# swbar002.net
KiCad netlist of a schematic drawn in EAGLE
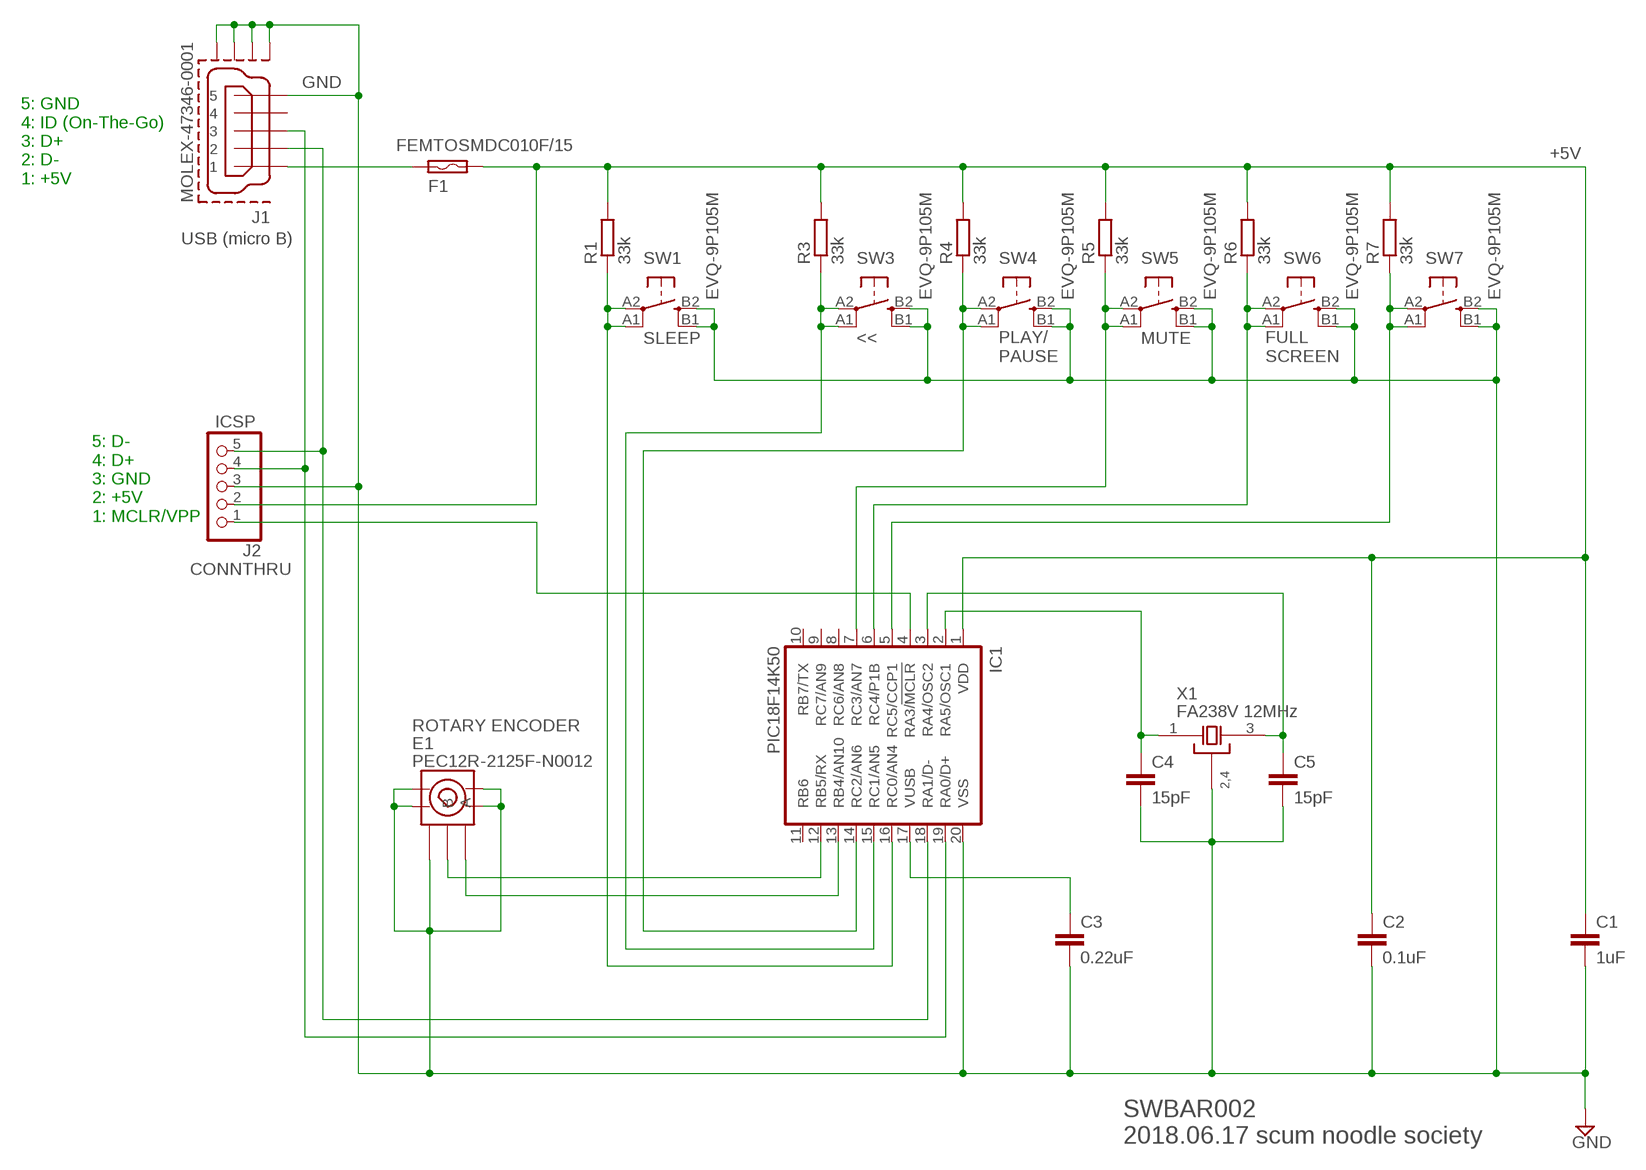
[diagram p0: schematic, sheet 1]

(export (version "E")
  (design (tool "Eeschema 10.0.6"))
  (components
    (comp (ref "C1")
      (value "1uF")
      (footprint "eagle-import:C0603K")
      (libsource (lib "eagle-import") (part "C-EUC0603K"))
    )
    (comp (ref "C2")
      (value "0.1uF")
      (footprint "eagle-import:C0603K")
      (libsource (lib "eagle-import") (part "C-EUC0603K"))
    )
    (comp (ref "C3")
      (value "0.22uF")
      (footprint "eagle-import:C0603K")
      (libsource (lib "eagle-import") (part "C-EUC0603K"))
    )
    (comp (ref "C4")
      (value "15pF")
      (footprint "eagle-import:C0603K")
      (libsource (lib "eagle-import") (part "C-EUC0603K"))
    )
    (comp (ref "C5")
      (value "15pF")
      (footprint "eagle-import:C0603K")
      (libsource (lib "eagle-import") (part "C-EUC0603K"))
    )
    (comp (ref "E1")
      (value "PEC12R-2125F-N0012")
      (footprint "eagle-import:PEC12R")
      (libsource (lib "eagle-import") (part "PEC12R-2125F-N0012"))
    )
    (comp (ref "F1")
      (value "FEMTOSMDC010F/15")
      (footprint "eagle-import:C0603K")
      (libsource (lib "eagle-import") (part "FEMTOSMDC010F/15"))
    )
    (comp (ref "IC1")
      (value "PIC18F14K50")
      (footprint "eagle-import:SSOP20")
      (libsource (lib "eagle-import") (part "PIC18F14K50"))
    )
    (comp (ref "J1")
      (value "MOLEX-47346-0001")
      (footprint "eagle-import:MOLEX-47364-0001")
      (libsource (lib "eagle-import") (part "MOLEX-47346-0001"))
    )
    (comp (ref "J2")
      (value "CONNTHRU")
      (footprint "eagle-import:1X05_CONNTHRU")
      (libsource (lib "eagle-import") (part "PINHD-1X51X05_CONNTHRU"))
    )
    (comp (ref "R1")
      (value "33k")
      (footprint "eagle-import:R0603")
      (libsource (lib "eagle-import") (part "R-EU_R0603"))
    )
    (comp (ref "R3")
      (value "33k")
      (footprint "eagle-import:R0603")
      (libsource (lib "eagle-import") (part "R-EU_R0603"))
    )
    (comp (ref "R4")
      (value "33k")
      (footprint "eagle-import:R0603")
      (libsource (lib "eagle-import") (part "R-EU_R0603"))
    )
    (comp (ref "R5")
      (value "33k")
      (footprint "eagle-import:R0603")
      (libsource (lib "eagle-import") (part "R-EU_R0603"))
    )
    (comp (ref "R6")
      (value "33k")
      (footprint "eagle-import:R0603")
      (libsource (lib "eagle-import") (part "R-EU_R0603"))
    )
    (comp (ref "R7")
      (value "33k")
      (footprint "eagle-import:R0603")
      (libsource (lib "eagle-import") (part "R-EU_R0603"))
    )
    (comp (ref "SW1")
      (value "EVQ-9P105M")
      (footprint "eagle-import:EVQ9P")
      (libsource (lib "eagle-import") (part "EVQ-9P105M"))
    )
    (comp (ref "SW3")
      (value "EVQ-9P105M")
      (footprint "eagle-import:EVQ9P")
      (libsource (lib "eagle-import") (part "EVQ-9P105M"))
    )
    (comp (ref "SW4")
      (value "EVQ-9P105M")
      (footprint "eagle-import:EVQ9P")
      (libsource (lib "eagle-import") (part "EVQ-9P105M"))
    )
    (comp (ref "SW5")
      (value "EVQ-9P105M")
      (footprint "eagle-import:EVQ9P")
      (libsource (lib "eagle-import") (part "EVQ-9P105M"))
    )
    (comp (ref "SW6")
      (value "EVQ-9P105M")
      (footprint "eagle-import:EVQ9P")
      (libsource (lib "eagle-import") (part "EVQ-9P105M"))
    )
    (comp (ref "SW7")
      (value "EVQ-9P105M")
      (footprint "eagle-import:EVQ9P")
      (libsource (lib "eagle-import") (part "EVQ-9P105M"))
    )
    (comp (ref "X1")
      (value "FA238V 12MHz")
      (footprint "eagle-import:XTAL_SMD_32X25")
      (libsource (lib "eagle-import") (part "FA-238V"))
    )
  )
  (nets
    (net (code "1") (name "/+5V") (class "Default")
      (node (ref "C1") (pin "1") (pinfunction "1_1") (pintype "passive"))
      (node (ref "C2") (pin "1") (pinfunction "1_1") (pintype "passive"))
      (node (ref "F1") (pin "2") (pinfunction "2_2") (pintype "passive"))
      (node (ref "IC1") (pin "1") (pinfunction "VDD_1") (pintype "power_in"))
      (node (ref "J2") (pin "2") (pinfunction "2_2") (pintype "passive"))
      (node (ref "R1") (pin "2") (pinfunction "2_2") (pintype "passive"))
      (node (ref "R3") (pin "2") (pinfunction "2_2") (pintype "passive"))
      (node (ref "R4") (pin "2") (pinfunction "2_2") (pintype "passive"))
      (node (ref "R5") (pin "2") (pinfunction "2_2") (pintype "passive"))
      (node (ref "R6") (pin "2") (pinfunction "2_2") (pintype "passive"))
      (node (ref "R7") (pin "2") (pinfunction "2_2") (pintype "passive"))
    )
    (net (code "2") (name "GND") (class "Default")
      (node (ref "C1") (pin "2") (pinfunction "2_2") (pintype "passive"))
      (node (ref "C2") (pin "2") (pinfunction "2_2") (pintype "passive"))
      (node (ref "C3") (pin "2") (pinfunction "2_2") (pintype "passive"))
      (node (ref "C4") (pin "2") (pinfunction "2_2") (pintype "passive"))
      (node (ref "C5") (pin "2") (pinfunction "2_2") (pintype "passive"))
      (node (ref "E1") (pin "GND@1") (pinfunction "GND_GND@1") (pintype "power_in"))
      (node (ref "E1") (pin "GND@2") (pinfunction "GND_GND@2") (pintype "power_in"))
      (node (ref "E1") (pin "GND@3") (pinfunction "GND_GND@3") (pintype "power_in"))
      (node (ref "E1") (pin "GND@4") (pinfunction "GND_GND@4") (pintype "power_in"))
      (node (ref "E1") (pin "GND@5") (pinfunction "GND_GND@5") (pintype "power_in"))
      (node (ref "IC1") (pin "20") (pinfunction "VSS_20") (pintype "power_in"))
      (node (ref "J1") (pin "5") (pinfunction "5_5") (pintype "input"))
      (node (ref "J1") (pin "GND1") (pinfunction "GND_GND1") (pintype "bidirectional"))
      (node (ref "J1") (pin "GND2") (pinfunction "GND_GND2") (pintype "bidirectional"))
      (node (ref "J1") (pin "GND3") (pinfunction "GND_GND3") (pintype "bidirectional"))
      (node (ref "J1") (pin "GND4") (pinfunction "GND_GND4") (pintype "bidirectional"))
      (node (ref "J2") (pin "3") (pinfunction "3_3") (pintype "passive"))
      (node (ref "SW1") (pin "B1") (pinfunction "G$S1_B1") (pintype "passive"))
      (node (ref "SW1") (pin "B2") (pinfunction "G$S2_B2") (pintype "passive"))
      (node (ref "SW3") (pin "B1") (pinfunction "G$S1_B1") (pintype "passive"))
      (node (ref "SW3") (pin "B2") (pinfunction "G$S2_B2") (pintype "passive"))
      (node (ref "SW4") (pin "B1") (pinfunction "G$S1_B1") (pintype "passive"))
      (node (ref "SW4") (pin "B2") (pinfunction "G$S2_B2") (pintype "passive"))
      (node (ref "SW5") (pin "B1") (pinfunction "G$S1_B1") (pintype "passive"))
      (node (ref "SW5") (pin "B2") (pinfunction "G$S2_B2") (pintype "passive"))
      (node (ref "SW6") (pin "B1") (pinfunction "G$S1_B1") (pintype "passive"))
      (node (ref "SW6") (pin "B2") (pinfunction "G$S2_B2") (pintype "passive"))
      (node (ref "SW7") (pin "B1") (pinfunction "G$S1_B1") (pintype "passive"))
      (node (ref "SW7") (pin "B2") (pinfunction "G$S2_B2") (pintype "passive"))
      (node (ref "X1") (pin "2") (pinfunction "GND_2") (pintype "power_in"))
      (node (ref "X1") (pin "4") (pinfunction "GND_4") (pintype "power_in"))
    )
    (net (code "3") (name "Net-(F1-Pad1)") (class "Default")
      (node (ref "F1") (pin "1") (pinfunction "1_1") (pintype "passive"))
      (node (ref "J1") (pin "1") (pinfunction "1_1") (pintype "input"))
    )
    (net (code "4") (name "Net-(IC1-RA0{slash}D+)") (class "Default")
      (node (ref "IC1") (pin "19") (pinfunction "RA0/D+_19") (pintype "bidirectional"))
      (node (ref "J1") (pin "3") (pinfunction "3_3") (pintype "input"))
      (node (ref "J2") (pin "4") (pinfunction "4_4") (pintype "passive"))
    )
    (net (code "5") (name "Net-(IC1-RA1{slash}D-)") (class "Default")
      (node (ref "IC1") (pin "18") (pinfunction "RA1/D-_18") (pintype "bidirectional"))
      (node (ref "J1") (pin "2") (pinfunction "2_2") (pintype "input"))
      (node (ref "J2") (pin "5") (pinfunction "5_5") (pintype "passive"))
    )
    (net (code "6") (name "Net-(IC1-RA3{slash}~{MCLR})") (class "Default")
      (node (ref "IC1") (pin "4") (pinfunction "RA3/~{MCLR}_4") (pintype "bidirectional"))
      (node (ref "J2") (pin "1") (pinfunction "1_1") (pintype "passive"))
    )
    (net (code "7") (name "Net-(IC1-RA4{slash}OSC2)") (class "Default")
      (node (ref "C5") (pin "1") (pinfunction "1_1") (pintype "passive"))
      (node (ref "IC1") (pin "3") (pinfunction "RA4/OSC2_3") (pintype "bidirectional"))
      (node (ref "X1") (pin "3") (pinfunction "X3_3") (pintype "bidirectional"))
    )
    (net (code "8") (name "Net-(IC1-RA5{slash}OSC1)") (class "Default")
      (node (ref "C4") (pin "1") (pinfunction "1_1") (pintype "passive"))
      (node (ref "IC1") (pin "2") (pinfunction "RA5/OSC1_2") (pintype "bidirectional"))
      (node (ref "X1") (pin "1") (pinfunction "X1_1") (pintype "bidirectional"))
    )
    (net (code "9") (name "Net-(IC1-RB4{slash}AN10)") (class "Default")
      (node (ref "E1") (pin "A") (pinfunction "A_A") (pintype "passive"))
      (node (ref "IC1") (pin "13") (pinfunction "RB4/AN10_13") (pintype "bidirectional"))
    )
    (net (code "10") (name "Net-(IC1-RB5{slash}RX)") (class "Default")
      (node (ref "E1") (pin "B") (pinfunction "B_B") (pintype "passive"))
      (node (ref "IC1") (pin "12") (pinfunction "RB5/RX_12") (pintype "bidirectional"))
    )
    (net (code "11") (name "Net-(IC1-RC0{slash}AN4)") (class "Default")
      (node (ref "IC1") (pin "16") (pinfunction "RC0/AN4_16") (pintype "bidirectional"))
      (node (ref "R1") (pin "1") (pinfunction "1_1") (pintype "passive"))
      (node (ref "SW1") (pin "A1") (pinfunction "G$P1_A1") (pintype "passive"))
      (node (ref "SW1") (pin "A2") (pinfunction "G$P2_A2") (pintype "passive"))
    )
    (net (code "12") (name "Net-(IC1-RC1{slash}AN5)") (class "Default")
      (node (ref "IC1") (pin "15") (pinfunction "RC1/AN5_15") (pintype "bidirectional"))
      (node (ref "R3") (pin "1") (pinfunction "1_1") (pintype "passive"))
      (node (ref "SW3") (pin "A1") (pinfunction "G$P1_A1") (pintype "passive"))
      (node (ref "SW3") (pin "A2") (pinfunction "G$P2_A2") (pintype "passive"))
    )
    (net (code "13") (name "Net-(IC1-RC2{slash}AN6)") (class "Default")
      (node (ref "IC1") (pin "14") (pinfunction "RC2/AN6_14") (pintype "bidirectional"))
      (node (ref "R4") (pin "1") (pinfunction "1_1") (pintype "passive"))
      (node (ref "SW4") (pin "A1") (pinfunction "G$P1_A1") (pintype "passive"))
      (node (ref "SW4") (pin "A2") (pinfunction "G$P2_A2") (pintype "passive"))
    )
    (net (code "14") (name "Net-(IC1-RC3{slash}AN7)") (class "Default")
      (node (ref "IC1") (pin "7") (pinfunction "RC3/AN7_7") (pintype "bidirectional"))
      (node (ref "R5") (pin "1") (pinfunction "1_1") (pintype "passive"))
      (node (ref "SW5") (pin "A1") (pinfunction "G$P1_A1") (pintype "passive"))
      (node (ref "SW5") (pin "A2") (pinfunction "G$P2_A2") (pintype "passive"))
    )
    (net (code "15") (name "Net-(IC1-RC4{slash}P1B)") (class "Default")
      (node (ref "IC1") (pin "6") (pinfunction "RC4/P1B_6") (pintype "bidirectional"))
      (node (ref "R6") (pin "1") (pinfunction "1_1") (pintype "passive"))
      (node (ref "SW6") (pin "A1") (pinfunction "G$P1_A1") (pintype "passive"))
      (node (ref "SW6") (pin "A2") (pinfunction "G$P2_A2") (pintype "passive"))
    )
    (net (code "16") (name "Net-(IC1-RC5{slash}CCP1)") (class "Default")
      (node (ref "IC1") (pin "5") (pinfunction "RC5/CCP1_5") (pintype "bidirectional"))
      (node (ref "R7") (pin "1") (pinfunction "1_1") (pintype "passive"))
      (node (ref "SW7") (pin "A1") (pinfunction "G$P1_A1") (pintype "passive"))
      (node (ref "SW7") (pin "A2") (pinfunction "G$P2_A2") (pintype "passive"))
    )
    (net (code "17") (name "Net-(IC1-VUSB)") (class "Default")
      (node (ref "C3") (pin "1") (pinfunction "1_1") (pintype "passive"))
      (node (ref "IC1") (pin "17") (pinfunction "VUSB_17") (pintype "bidirectional"))
    )
    (net (code "18") (name "unconnected-(IC1-RB6-Pad11)") (class "Default")
      (node (ref "IC1") (pin "11") (pinfunction "RB6_11") (pintype "bidirectional"))
    )
    (net (code "19") (name "unconnected-(IC1-RB7{slash}TX-Pad10)") (class "Default")
      (node (ref "IC1") (pin "10") (pinfunction "RB7/TX_10") (pintype "bidirectional"))
    )
    (net (code "20") (name "unconnected-(IC1-RC6{slash}AN8-Pad8)") (class "Default")
      (node (ref "IC1") (pin "8") (pinfunction "RC6/AN8_8") (pintype "bidirectional"))
    )
    (net (code "21") (name "unconnected-(IC1-RC7{slash}AN9-Pad9)") (class "Default")
      (node (ref "IC1") (pin "9") (pinfunction "RC7/AN9_9") (pintype "bidirectional"))
    )
    (net (code "22") (name "unconnected-(J1-Pad4)") (class "Default")
      (node (ref "J1") (pin "4") (pinfunction "4_4") (pintype "input"))
    )
  )
)
